# TriacFanout.net
KiCad netlist of a schematic drawn in EAGLE
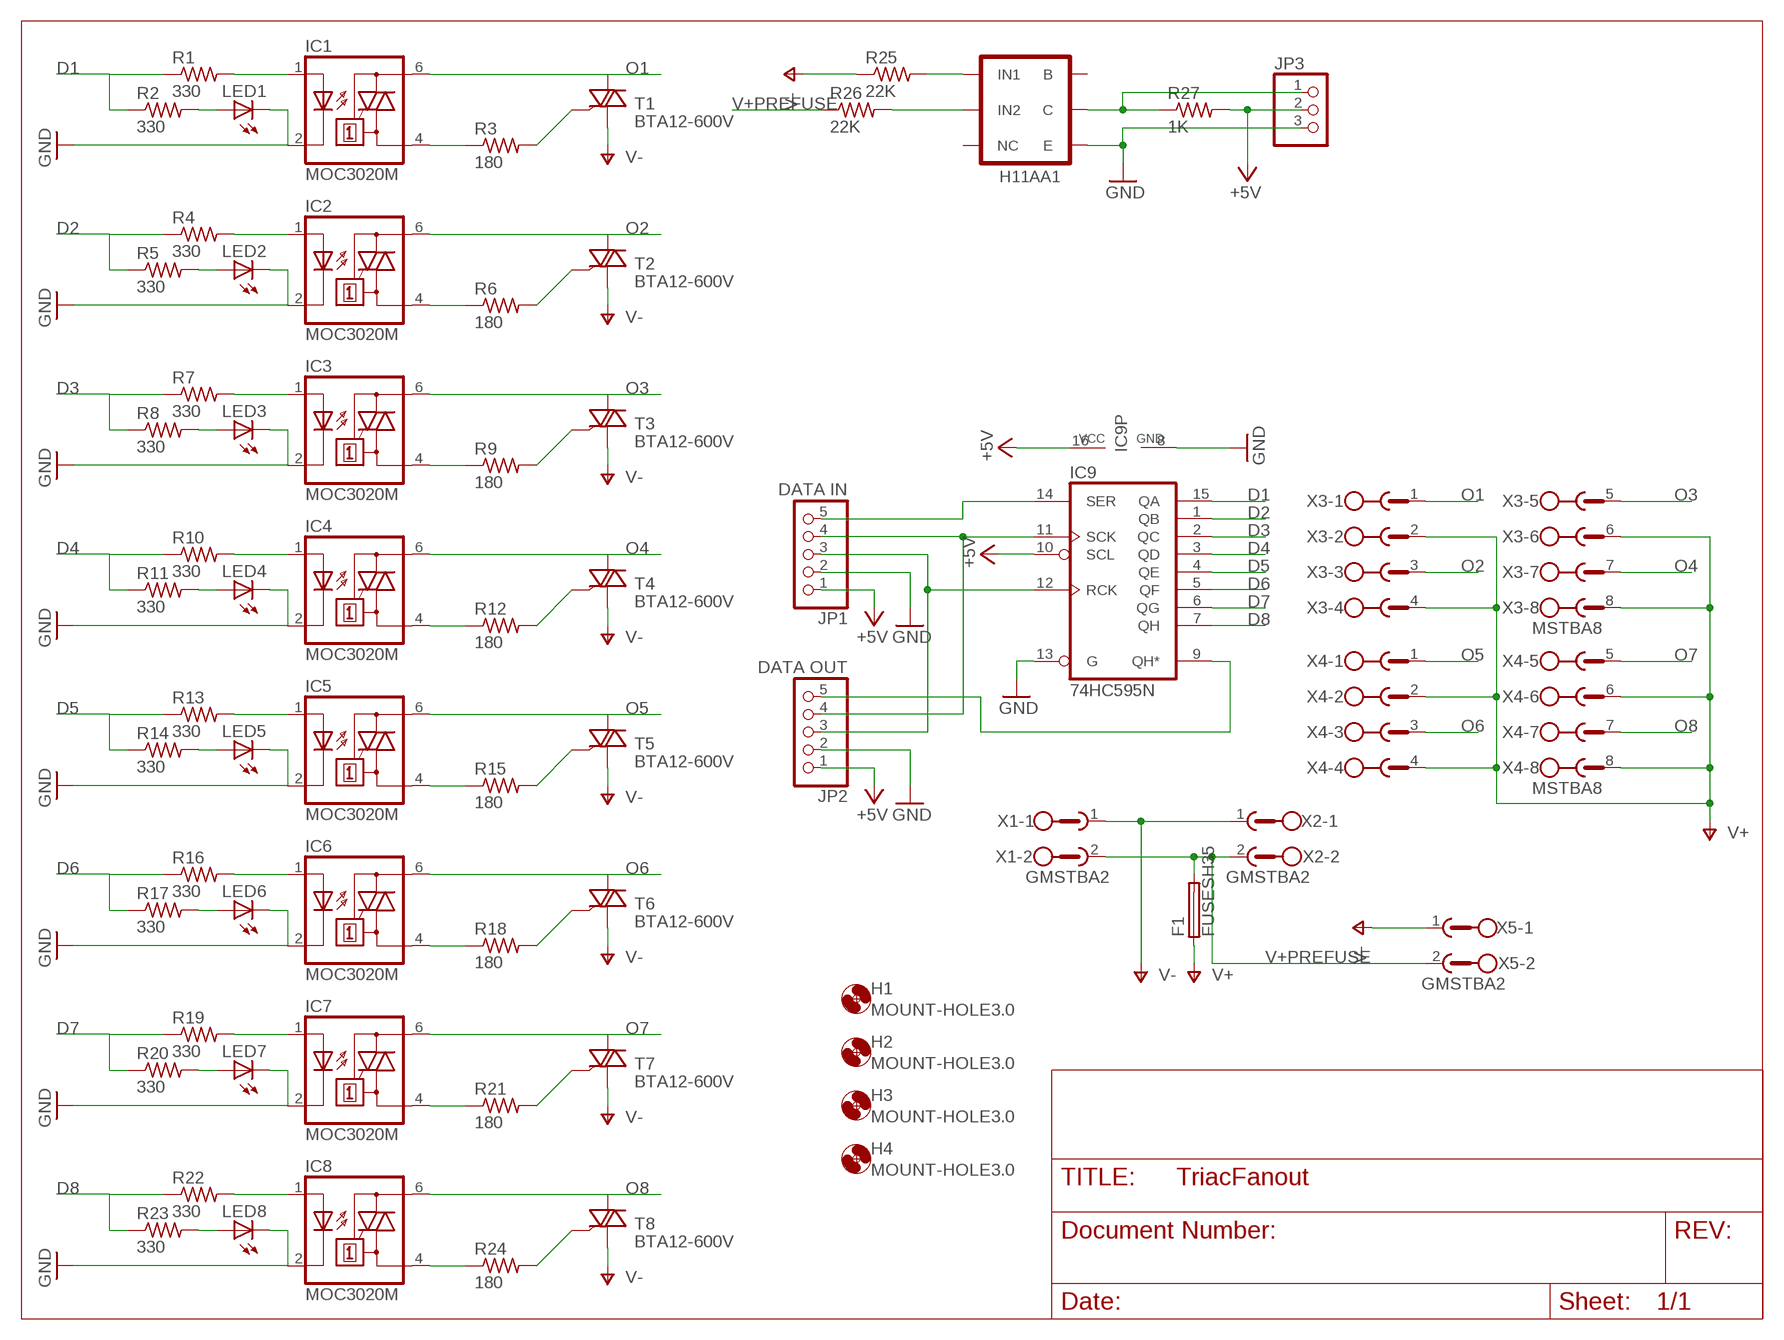
[diagram p0: schematic, sheet 1]

(export (version "E")
  (design (tool "Eeschema 10.0.6"))
  (components
    (comp (ref "F1")
      (value "FUSESH35")
      (footprint "eagle-import:SH25")
      (libsource (lib "eagle-import") (part "FUSESH35"))
    )
    (comp (ref "H1")
      (value "MOUNT-HOLE3.0")
      (footprint "eagle-import:3,0")
      (libsource (lib "eagle-import") (part "MOUNT-HOLE3.0"))
    )
    (comp (ref "H2")
      (value "MOUNT-HOLE3.0")
      (footprint "eagle-import:3,0")
      (libsource (lib "eagle-import") (part "MOUNT-HOLE3.0"))
    )
    (comp (ref "H3")
      (value "MOUNT-HOLE3.0")
      (footprint "eagle-import:3,0")
      (libsource (lib "eagle-import") (part "MOUNT-HOLE3.0"))
    )
    (comp (ref "H4")
      (value "MOUNT-HOLE3.0")
      (footprint "eagle-import:3,0")
      (libsource (lib "eagle-import") (part "MOUNT-HOLE3.0"))
    )
    (comp (ref "IC1")
      (value "MOC3020M")
      (footprint "eagle-import:DIL06")
      (fields (field (name "MF") "FAIRCHILD SEMICONDUCTOR") (field (name "MPN") "MOC3020-M"))
      (libsource (lib "eagle-import") (part "MOC30M20"))
    )
    (comp (ref "IC2")
      (value "MOC3020M")
      (footprint "eagle-import:DIL06")
      (fields (field (name "MF") "FAIRCHILD SEMICONDUCTOR") (field (name "MPN") "MOC3020-M"))
      (libsource (lib "eagle-import") (part "MOC30M20"))
    )
    (comp (ref "IC3")
      (value "MOC3020M")
      (footprint "eagle-import:DIL06")
      (fields (field (name "MF") "FAIRCHILD SEMICONDUCTOR") (field (name "MPN") "MOC3020-M"))
      (libsource (lib "eagle-import") (part "MOC30M20"))
    )
    (comp (ref "IC4")
      (value "MOC3020M")
      (footprint "eagle-import:DIL06")
      (fields (field (name "MF") "FAIRCHILD SEMICONDUCTOR") (field (name "MPN") "MOC3020-M"))
      (libsource (lib "eagle-import") (part "MOC30M20"))
    )
    (comp (ref "IC5")
      (value "MOC3020M")
      (footprint "eagle-import:DIL06")
      (fields (field (name "MF") "FAIRCHILD SEMICONDUCTOR") (field (name "MPN") "MOC3020-M"))
      (libsource (lib "eagle-import") (part "MOC30M20"))
    )
    (comp (ref "IC6")
      (value "MOC3020M")
      (footprint "eagle-import:DIL06")
      (fields (field (name "MF") "FAIRCHILD SEMICONDUCTOR") (field (name "MPN") "MOC3020-M"))
      (libsource (lib "eagle-import") (part "MOC30M20"))
    )
    (comp (ref "IC7")
      (value "MOC3020M")
      (footprint "eagle-import:DIL06")
      (fields (field (name "MF") "FAIRCHILD SEMICONDUCTOR") (field (name "MPN") "MOC3020-M"))
      (libsource (lib "eagle-import") (part "MOC30M20"))
    )
    (comp (ref "IC8")
      (value "MOC3020M")
      (footprint "eagle-import:DIL06")
      (fields (field (name "MF") "FAIRCHILD SEMICONDUCTOR") (field (name "MPN") "MOC3020-M"))
      (libsource (lib "eagle-import") (part "MOC30M20"))
    )
    (comp (ref "IC9")
      (value "74HC595N")
      (footprint "eagle-import:DIL16")
      (libsource (lib "eagle-import") (part "74595NHC"))
    )
    (comp (ref "JP1")
      (value "DATA IN")
      (footprint "eagle-import:1X05")
      (libsource (lib "eagle-import") (part "PINHD-1X5"))
    )
    (comp (ref "JP2")
      (value "DATA OUT")
      (footprint "eagle-import:1X05")
      (libsource (lib "eagle-import") (part "PINHD-1X5"))
    )
    (comp (ref "JP3")
      (value "PINHD-1X3")
      (footprint "eagle-import:1X03")
      (libsource (lib "eagle-import") (part "PINHD-1X3"))
    )
    (comp (ref "LED1")
      (value "LED5MM")
      (footprint "eagle-import:LED5MM")
      (libsource (lib "eagle-import") (part "LED5MM"))
    )
    (comp (ref "LED2")
      (value "LED5MM")
      (footprint "eagle-import:LED5MM")
      (libsource (lib "eagle-import") (part "LED5MM"))
    )
    (comp (ref "LED3")
      (value "LED5MM")
      (footprint "eagle-import:LED5MM")
      (libsource (lib "eagle-import") (part "LED5MM"))
    )
    (comp (ref "LED4")
      (value "LED5MM")
      (footprint "eagle-import:LED5MM")
      (libsource (lib "eagle-import") (part "LED5MM"))
    )
    (comp (ref "LED5")
      (value "LED5MM")
      (footprint "eagle-import:LED5MM")
      (libsource (lib "eagle-import") (part "LED5MM"))
    )
    (comp (ref "LED6")
      (value "LED5MM")
      (footprint "eagle-import:LED5MM")
      (libsource (lib "eagle-import") (part "LED5MM"))
    )
    (comp (ref "LED7")
      (value "LED5MM")
      (footprint "eagle-import:LED5MM")
      (libsource (lib "eagle-import") (part "LED5MM"))
    )
    (comp (ref "LED8")
      (value "LED5MM")
      (footprint "eagle-import:LED5MM")
      (libsource (lib "eagle-import") (part "LED5MM"))
    )
    (comp (ref "R1")
      (value "330")
      (footprint "eagle-import:0207_10")
      (libsource (lib "eagle-import") (part "R-US_0207/10"))
    )
    (comp (ref "R2")
      (value "330")
      (footprint "eagle-import:0207_10")
      (libsource (lib "eagle-import") (part "R-US_0207/10"))
    )
    (comp (ref "R3")
      (value "180")
      (footprint "eagle-import:0207_10")
      (libsource (lib "eagle-import") (part "R-US_0207/10"))
    )
    (comp (ref "R4")
      (value "330")
      (footprint "eagle-import:0207_10")
      (libsource (lib "eagle-import") (part "R-US_0207/10"))
    )
    (comp (ref "R5")
      (value "330")
      (footprint "eagle-import:0207_10")
      (libsource (lib "eagle-import") (part "R-US_0207/10"))
    )
    (comp (ref "R6")
      (value "180")
      (footprint "eagle-import:0207_10")
      (libsource (lib "eagle-import") (part "R-US_0207/10"))
    )
    (comp (ref "R7")
      (value "330")
      (footprint "eagle-import:0207_10")
      (libsource (lib "eagle-import") (part "R-US_0207/10"))
    )
    (comp (ref "R8")
      (value "330")
      (footprint "eagle-import:0207_10")
      (libsource (lib "eagle-import") (part "R-US_0207/10"))
    )
    (comp (ref "R9")
      (value "180")
      (footprint "eagle-import:0207_10")
      (libsource (lib "eagle-import") (part "R-US_0207/10"))
    )
    (comp (ref "R10")
      (value "330")
      (footprint "eagle-import:0207_10")
      (libsource (lib "eagle-import") (part "R-US_0207/10"))
    )
    (comp (ref "R11")
      (value "330")
      (footprint "eagle-import:0207_10")
      (libsource (lib "eagle-import") (part "R-US_0207/10"))
    )
    (comp (ref "R12")
      (value "180")
      (footprint "eagle-import:0207_10")
      (libsource (lib "eagle-import") (part "R-US_0207/10"))
    )
    (comp (ref "R13")
      (value "330")
      (footprint "eagle-import:0207_10")
      (libsource (lib "eagle-import") (part "R-US_0207/10"))
    )
    (comp (ref "R14")
      (value "330")
      (footprint "eagle-import:0207_10")
      (libsource (lib "eagle-import") (part "R-US_0207/10"))
    )
    (comp (ref "R15")
      (value "180")
      (footprint "eagle-import:0207_10")
      (libsource (lib "eagle-import") (part "R-US_0207/10"))
    )
    (comp (ref "R16")
      (value "330")
      (footprint "eagle-import:0207_10")
      (libsource (lib "eagle-import") (part "R-US_0207/10"))
    )
    (comp (ref "R17")
      (value "330")
      (footprint "eagle-import:0207_10")
      (libsource (lib "eagle-import") (part "R-US_0207/10"))
    )
    (comp (ref "R18")
      (value "180")
      (footprint "eagle-import:0207_10")
      (libsource (lib "eagle-import") (part "R-US_0207/10"))
    )
    (comp (ref "R19")
      (value "330")
      (footprint "eagle-import:0207_10")
      (libsource (lib "eagle-import") (part "R-US_0207/10"))
    )
    (comp (ref "R20")
      (value "330")
      (footprint "eagle-import:0207_10")
      (libsource (lib "eagle-import") (part "R-US_0207/10"))
    )
    (comp (ref "R21")
      (value "180")
      (footprint "eagle-import:0207_10")
      (libsource (lib "eagle-import") (part "R-US_0207/10"))
    )
    (comp (ref "R22")
      (value "330")
      (footprint "eagle-import:0207_10")
      (libsource (lib "eagle-import") (part "R-US_0207/10"))
    )
    (comp (ref "R23")
      (value "330")
      (footprint "eagle-import:0207_10")
      (libsource (lib "eagle-import") (part "R-US_0207/10"))
    )
    (comp (ref "R24")
      (value "180")
      (footprint "eagle-import:0207_10")
      (libsource (lib "eagle-import") (part "R-US_0207/10"))
    )
    (comp (ref "R25")
      (value "22K")
      (footprint "eagle-import:0411_12")
      (libsource (lib "eagle-import") (part "R-US_0411/12"))
    )
    (comp (ref "R26")
      (value "22K")
      (footprint "eagle-import:0411_12")
      (libsource (lib "eagle-import") (part "R-US_0411/12"))
    )
    (comp (ref "R27")
      (value "1K")
      (footprint "eagle-import:0207_10")
      (libsource (lib "eagle-import") (part "R-US_0207/10"))
    )
    (comp (ref "T1")
      (value "BTA12-600V")
      (footprint "eagle-import:TO220V")
      (libsource (lib "eagle-import") (part "BTA12-600V"))
    )
    (comp (ref "T2")
      (value "BTA12-600V")
      (footprint "eagle-import:TO220V")
      (libsource (lib "eagle-import") (part "BTA12-600V"))
    )
    (comp (ref "T3")
      (value "BTA12-600V")
      (footprint "eagle-import:TO220V")
      (libsource (lib "eagle-import") (part "BTA12-600V"))
    )
    (comp (ref "T4")
      (value "BTA12-600V")
      (footprint "eagle-import:TO220V")
      (libsource (lib "eagle-import") (part "BTA12-600V"))
    )
    (comp (ref "T5")
      (value "BTA12-600V")
      (footprint "eagle-import:TO220V")
      (libsource (lib "eagle-import") (part "BTA12-600V"))
    )
    (comp (ref "T6")
      (value "BTA12-600V")
      (footprint "eagle-import:TO220V")
      (libsource (lib "eagle-import") (part "BTA12-600V"))
    )
    (comp (ref "T7")
      (value "BTA12-600V")
      (footprint "eagle-import:TO220V")
      (libsource (lib "eagle-import") (part "BTA12-600V"))
    )
    (comp (ref "T8")
      (value "BTA12-600V")
      (footprint "eagle-import:TO220V")
      (libsource (lib "eagle-import") (part "BTA12-600V"))
    )
    (comp (ref "U$1")
      (value "H11AA1")
      (footprint "eagle-import:DIL06")
      (libsource (lib "eagle-import") (part "H11AA1"))
    )
    (comp (ref "X1")
      (value "GMSTBA2")
      (footprint "eagle-import:GMSTBA2")
      (fields (field (name "MF") "FARNELL") (field (name "MPN") "1757242"))
      (libsource (lib "eagle-import") (part "GMSTBA2"))
    )
    (comp (ref "X2")
      (value "GMSTBA2")
      (footprint "eagle-import:GMSTBA2")
      (fields (field (name "MF") "FARNELL") (field (name "MPN") "1757242"))
      (libsource (lib "eagle-import") (part "GMSTBA2"))
    )
    (comp (ref "X3")
      (value "MSTBA8")
      (footprint "eagle-import:MSTBA8")
      (fields (field (name "MF") "FARNELL") (field (name "MPN") "1757307"))
      (libsource (lib "eagle-import") (part "MSTBA8"))
    )
    (comp (ref "X4")
      (value "MSTBA8")
      (footprint "eagle-import:MSTBA8")
      (fields (field (name "MF") "FARNELL") (field (name "MPN") "1757307"))
      (libsource (lib "eagle-import") (part "MSTBA8"))
    )
    (comp (ref "X5")
      (value "GMSTBA2")
      (footprint "eagle-import:GMSTBA2")
      (fields (field (name "MF") "FARNELL") (field (name "MPN") "1757242"))
      (libsource (lib "eagle-import") (part "GMSTBA2"))
    )
  )
  (nets
    (net (code "1") (name "+5V") (class "Default")
      (node (ref "IC9") (pin "10") (pinfunction "SCL_10") (pintype "input"))
      (node (ref "IC9") (pin "16") (pinfunction "VCC_16") (pintype "power_in"))
      (node (ref "JP1") (pin "1") (pinfunction "1_1") (pintype "passive"))
      (node (ref "JP2") (pin "1") (pinfunction "1_1") (pintype "passive"))
      (node (ref "JP3") (pin "2") (pinfunction "2_2") (pintype "passive"))
      (node (ref "R27") (pin "2") (pinfunction "2_2") (pintype "passive"))
    )
    (net (code "2") (name "/D1") (class "Default")
      (node (ref "IC9") (pin "15") (pinfunction "QA_15") (pintype "tri_state"))
      (node (ref "R1") (pin "1") (pinfunction "1_1") (pintype "passive"))
      (node (ref "R2") (pin "1") (pinfunction "1_1") (pintype "passive"))
    )
    (net (code "3") (name "/D2") (class "Default")
      (node (ref "IC9") (pin "1") (pinfunction "QB_1") (pintype "tri_state"))
      (node (ref "R4") (pin "1") (pinfunction "1_1") (pintype "passive"))
      (node (ref "R5") (pin "1") (pinfunction "1_1") (pintype "passive"))
    )
    (net (code "4") (name "/D3") (class "Default")
      (node (ref "IC9") (pin "2") (pinfunction "QC_2") (pintype "tri_state"))
      (node (ref "R7") (pin "1") (pinfunction "1_1") (pintype "passive"))
      (node (ref "R8") (pin "1") (pinfunction "1_1") (pintype "passive"))
    )
    (net (code "5") (name "/D4") (class "Default")
      (node (ref "IC9") (pin "3") (pinfunction "QD_3") (pintype "tri_state"))
      (node (ref "R10") (pin "1") (pinfunction "1_1") (pintype "passive"))
      (node (ref "R11") (pin "1") (pinfunction "1_1") (pintype "passive"))
    )
    (net (code "6") (name "/D5") (class "Default")
      (node (ref "IC9") (pin "4") (pinfunction "QE_4") (pintype "tri_state"))
      (node (ref "R13") (pin "1") (pinfunction "1_1") (pintype "passive"))
      (node (ref "R14") (pin "1") (pinfunction "1_1") (pintype "passive"))
    )
    (net (code "7") (name "/D6") (class "Default")
      (node (ref "IC9") (pin "5") (pinfunction "QF_5") (pintype "tri_state"))
      (node (ref "R16") (pin "1") (pinfunction "1_1") (pintype "passive"))
      (node (ref "R17") (pin "1") (pinfunction "1_1") (pintype "passive"))
    )
    (net (code "8") (name "/D7") (class "Default")
      (node (ref "IC9") (pin "6") (pinfunction "QG_6") (pintype "tri_state"))
      (node (ref "R19") (pin "1") (pinfunction "1_1") (pintype "passive"))
      (node (ref "R20") (pin "1") (pinfunction "1_1") (pintype "passive"))
    )
    (net (code "9") (name "/D8") (class "Default")
      (node (ref "IC9") (pin "7") (pinfunction "QH_7") (pintype "tri_state"))
      (node (ref "R22") (pin "1") (pinfunction "1_1") (pintype "passive"))
      (node (ref "R23") (pin "1") (pinfunction "1_1") (pintype "passive"))
    )
    (net (code "10") (name "/O1") (class "Default")
      (node (ref "IC1") (pin "6") (pinfunction "A2_6") (pintype "passive"))
      (node (ref "T1") (pin "2") (pinfunction "A2_2") (pintype "passive"))
      (node (ref "X3") (pin "1") (pinfunction "1_1") (pintype "passive"))
    )
    (net (code "11") (name "/O2") (class "Default")
      (node (ref "IC2") (pin "6") (pinfunction "A2_6") (pintype "passive"))
      (node (ref "T2") (pin "2") (pinfunction "A2_2") (pintype "passive"))
      (node (ref "X3") (pin "3") (pinfunction "1_3") (pintype "passive"))
    )
    (net (code "12") (name "/O3") (class "Default")
      (node (ref "IC3") (pin "6") (pinfunction "A2_6") (pintype "passive"))
      (node (ref "T3") (pin "2") (pinfunction "A2_2") (pintype "passive"))
      (node (ref "X3") (pin "5") (pinfunction "1_5") (pintype "passive"))
    )
    (net (code "13") (name "/O4") (class "Default")
      (node (ref "IC4") (pin "6") (pinfunction "A2_6") (pintype "passive"))
      (node (ref "T4") (pin "2") (pinfunction "A2_2") (pintype "passive"))
      (node (ref "X3") (pin "7") (pinfunction "1_7") (pintype "passive"))
    )
    (net (code "14") (name "/O5") (class "Default")
      (node (ref "IC5") (pin "6") (pinfunction "A2_6") (pintype "passive"))
      (node (ref "T5") (pin "2") (pinfunction "A2_2") (pintype "passive"))
      (node (ref "X4") (pin "1") (pinfunction "1_1") (pintype "passive"))
    )
    (net (code "15") (name "/O6") (class "Default")
      (node (ref "IC6") (pin "6") (pinfunction "A2_6") (pintype "passive"))
      (node (ref "T6") (pin "2") (pinfunction "A2_2") (pintype "passive"))
      (node (ref "X4") (pin "3") (pinfunction "1_3") (pintype "passive"))
    )
    (net (code "16") (name "/O7") (class "Default")
      (node (ref "IC7") (pin "6") (pinfunction "A2_6") (pintype "passive"))
      (node (ref "T7") (pin "2") (pinfunction "A2_2") (pintype "passive"))
      (node (ref "X4") (pin "5") (pinfunction "1_5") (pintype "passive"))
    )
    (net (code "17") (name "/O8") (class "Default")
      (node (ref "IC8") (pin "6") (pinfunction "A2_6") (pintype "passive"))
      (node (ref "T8") (pin "2") (pinfunction "A2_2") (pintype "passive"))
      (node (ref "X4") (pin "7") (pinfunction "1_7") (pintype "passive"))
    )
    (net (code "18") (name "/V+PREFUSE") (class "Default")
      (node (ref "F1") (pin "2") (pinfunction "2_2") (pintype "passive"))
      (node (ref "R26") (pin "1") (pinfunction "1_1") (pintype "passive"))
      (node (ref "X1") (pin "2") (pinfunction "1_2") (pintype "passive"))
      (node (ref "X2") (pin "2") (pinfunction "1_2") (pintype "passive"))
      (node (ref "X5") (pin "2") (pinfunction "1_2") (pintype "passive"))
    )
    (net (code "19") (name "GND") (class "Default")
      (node (ref "IC1") (pin "2") (pinfunction "C_2") (pintype "passive"))
      (node (ref "IC2") (pin "2") (pinfunction "C_2") (pintype "passive"))
      (node (ref "IC3") (pin "2") (pinfunction "C_2") (pintype "passive"))
      (node (ref "IC4") (pin "2") (pinfunction "C_2") (pintype "passive"))
      (node (ref "IC5") (pin "2") (pinfunction "C_2") (pintype "passive"))
      (node (ref "IC6") (pin "2") (pinfunction "C_2") (pintype "passive"))
      (node (ref "IC7") (pin "2") (pinfunction "C_2") (pintype "passive"))
      (node (ref "IC8") (pin "2") (pinfunction "C_2") (pintype "passive"))
      (node (ref "IC9") (pin "13") (pinfunction "G_13") (pintype "input"))
      (node (ref "IC9") (pin "8") (pinfunction "GND_8") (pintype "power_in"))
      (node (ref "JP1") (pin "2") (pinfunction "2_2") (pintype "passive"))
      (node (ref "JP2") (pin "2") (pinfunction "2_2") (pintype "passive"))
      (node (ref "JP3") (pin "3") (pinfunction "3_3") (pintype "passive"))
      (node (ref "LED1") (pin "K") (pinfunction "C_K") (pintype "passive"))
      (node (ref "LED2") (pin "K") (pinfunction "C_K") (pintype "passive"))
      (node (ref "LED3") (pin "K") (pinfunction "C_K") (pintype "passive"))
      (node (ref "LED4") (pin "K") (pinfunction "C_K") (pintype "passive"))
      (node (ref "LED5") (pin "K") (pinfunction "C_K") (pintype "passive"))
      (node (ref "LED6") (pin "K") (pinfunction "C_K") (pintype "passive"))
      (node (ref "LED7") (pin "K") (pinfunction "C_K") (pintype "passive"))
      (node (ref "LED8") (pin "K") (pinfunction "C_K") (pintype "passive"))
      (node (ref "U$1") (pin "4") (pinfunction "E_4") (pintype "bidirectional"))
    )
    (net (code "20") (name "Net-(IC1-A)") (class "Default")
      (node (ref "IC1") (pin "1") (pinfunction "A_1") (pintype "passive"))
      (node (ref "R1") (pin "2") (pinfunction "2_2") (pintype "passive"))
    )
    (net (code "21") (name "Net-(IC1-A1)") (class "Default")
      (node (ref "IC1") (pin "4") (pinfunction "A1_4") (pintype "passive"))
      (node (ref "R3") (pin "1") (pinfunction "1_1") (pintype "passive"))
    )
    (net (code "22") (name "Net-(IC2-A)") (class "Default")
      (node (ref "IC2") (pin "1") (pinfunction "A_1") (pintype "passive"))
      (node (ref "R4") (pin "2") (pinfunction "2_2") (pintype "passive"))
    )
    (net (code "23") (name "Net-(IC2-A1)") (class "Default")
      (node (ref "IC2") (pin "4") (pinfunction "A1_4") (pintype "passive"))
      (node (ref "R6") (pin "1") (pinfunction "1_1") (pintype "passive"))
    )
    (net (code "24") (name "Net-(IC3-A)") (class "Default")
      (node (ref "IC3") (pin "1") (pinfunction "A_1") (pintype "passive"))
      (node (ref "R7") (pin "2") (pinfunction "2_2") (pintype "passive"))
    )
    (net (code "25") (name "Net-(IC3-A1)") (class "Default")
      (node (ref "IC3") (pin "4") (pinfunction "A1_4") (pintype "passive"))
      (node (ref "R9") (pin "1") (pinfunction "1_1") (pintype "passive"))
    )
    (net (code "26") (name "Net-(IC4-A)") (class "Default")
      (node (ref "IC4") (pin "1") (pinfunction "A_1") (pintype "passive"))
      (node (ref "R10") (pin "2") (pinfunction "2_2") (pintype "passive"))
    )
    (net (code "27") (name "Net-(IC4-A1)") (class "Default")
      (node (ref "IC4") (pin "4") (pinfunction "A1_4") (pintype "passive"))
      (node (ref "R12") (pin "1") (pinfunction "1_1") (pintype "passive"))
    )
    (net (code "28") (name "Net-(IC5-A)") (class "Default")
      (node (ref "IC5") (pin "1") (pinfunction "A_1") (pintype "passive"))
      (node (ref "R13") (pin "2") (pinfunction "2_2") (pintype "passive"))
    )
    (net (code "29") (name "Net-(IC5-A1)") (class "Default")
      (node (ref "IC5") (pin "4") (pinfunction "A1_4") (pintype "passive"))
      (node (ref "R15") (pin "1") (pinfunction "1_1") (pintype "passive"))
    )
    (net (code "30") (name "Net-(IC6-A)") (class "Default")
      (node (ref "IC6") (pin "1") (pinfunction "A_1") (pintype "passive"))
      (node (ref "R16") (pin "2") (pinfunction "2_2") (pintype "passive"))
    )
    (net (code "31") (name "Net-(IC6-A1)") (class "Default")
      (node (ref "IC6") (pin "4") (pinfunction "A1_4") (pintype "passive"))
      (node (ref "R18") (pin "1") (pinfunction "1_1") (pintype "passive"))
    )
    (net (code "32") (name "Net-(IC7-A)") (class "Default")
      (node (ref "IC7") (pin "1") (pinfunction "A_1") (pintype "passive"))
      (node (ref "R19") (pin "2") (pinfunction "2_2") (pintype "passive"))
    )
    (net (code "33") (name "Net-(IC7-A1)") (class "Default")
      (node (ref "IC7") (pin "4") (pinfunction "A1_4") (pintype "passive"))
      (node (ref "R21") (pin "1") (pinfunction "1_1") (pintype "passive"))
    )
    (net (code "34") (name "Net-(IC8-A)") (class "Default")
      (node (ref "IC8") (pin "1") (pinfunction "A_1") (pintype "passive"))
      (node (ref "R22") (pin "2") (pinfunction "2_2") (pintype "passive"))
    )
    (net (code "35") (name "Net-(IC8-A1)") (class "Default")
      (node (ref "IC8") (pin "4") (pinfunction "A1_4") (pintype "passive"))
      (node (ref "R24") (pin "1") (pinfunction "1_1") (pintype "passive"))
    )
    (net (code "36") (name "Net-(IC9A-QH*)") (class "Default")
      (node (ref "IC9") (pin "9") (pinfunction "QH*_9") (pintype "tri_state"))
      (node (ref "JP2") (pin "5") (pinfunction "5_5") (pintype "passive"))
    )
    (net (code "37") (name "Net-(IC9A-RCK)") (class "Default")
      (node (ref "IC9") (pin "12") (pinfunction "RCK_12") (pintype "input"))
      (node (ref "JP1") (pin "3") (pinfunction "3_3") (pintype "passive"))
      (node (ref "JP2") (pin "3") (pinfunction "3_3") (pintype "passive"))
    )
    (net (code "38") (name "Net-(IC9A-SCK)") (class "Default")
      (node (ref "IC9") (pin "11") (pinfunction "SCK_11") (pintype "input"))
      (node (ref "JP1") (pin "4") (pinfunction "4_4") (pintype "passive"))
      (node (ref "JP2") (pin "4") (pinfunction "4_4") (pintype "passive"))
    )
    (net (code "39") (name "Net-(IC9A-SER)") (class "Default")
      (node (ref "IC9") (pin "14") (pinfunction "SER_14") (pintype "input"))
      (node (ref "JP1") (pin "5") (pinfunction "5_5") (pintype "passive"))
    )
    (net (code "40") (name "Net-(LED1-PadA)") (class "Default")
      (node (ref "LED1") (pin "A") (pinfunction "A_A") (pintype "passive"))
      (node (ref "R2") (pin "2") (pinfunction "2_2") (pintype "passive"))
    )
    (net (code "41") (name "Net-(LED2-PadA)") (class "Default")
      (node (ref "LED2") (pin "A") (pinfunction "A_A") (pintype "passive"))
      (node (ref "R5") (pin "2") (pinfunction "2_2") (pintype "passive"))
    )
    (net (code "42") (name "Net-(LED3-PadA)") (class "Default")
      (node (ref "LED3") (pin "A") (pinfunction "A_A") (pintype "passive"))
      (node (ref "R8") (pin "2") (pinfunction "2_2") (pintype "passive"))
    )
    (net (code "43") (name "Net-(LED4-PadA)") (class "Default")
      (node (ref "LED4") (pin "A") (pinfunction "A_A") (pintype "passive"))
      (node (ref "R11") (pin "2") (pinfunction "2_2") (pintype "passive"))
    )
    (net (code "44") (name "Net-(LED5-PadA)") (class "Default")
      (node (ref "LED5") (pin "A") (pinfunction "A_A") (pintype "passive"))
      (node (ref "R14") (pin "2") (pinfunction "2_2") (pintype "passive"))
    )
    (net (code "45") (name "Net-(LED6-PadA)") (class "Default")
      (node (ref "LED6") (pin "A") (pinfunction "A_A") (pintype "passive"))
      (node (ref "R17") (pin "2") (pinfunction "2_2") (pintype "passive"))
    )
    (net (code "46") (name "Net-(LED7-PadA)") (class "Default")
      (node (ref "LED7") (pin "A") (pinfunction "A_A") (pintype "passive"))
      (node (ref "R20") (pin "2") (pinfunction "2_2") (pintype "passive"))
    )
    (net (code "47") (name "Net-(LED8-PadA)") (class "Default")
      (node (ref "LED8") (pin "A") (pinfunction "A_A") (pintype "passive"))
      (node (ref "R23") (pin "2") (pinfunction "2_2") (pintype "passive"))
    )
    (net (code "48") (name "Net-(T1-G)") (class "Default")
      (node (ref "R3") (pin "2") (pinfunction "2_2") (pintype "passive"))
      (node (ref "T1") (pin "3") (pinfunction "G_3") (pintype "passive"))
    )
    (net (code "49") (name "Net-(T2-G)") (class "Default")
      (node (ref "R6") (pin "2") (pinfunction "2_2") (pintype "passive"))
      (node (ref "T2") (pin "3") (pinfunction "G_3") (pintype "passive"))
    )
    (net (code "50") (name "Net-(T3-G)") (class "Default")
      (node (ref "R9") (pin "2") (pinfunction "2_2") (pintype "passive"))
      (node (ref "T3") (pin "3") (pinfunction "G_3") (pintype "passive"))
    )
    (net (code "51") (name "Net-(T4-G)") (class "Default")
      (node (ref "R12") (pin "2") (pinfunction "2_2") (pintype "passive"))
      (node (ref "T4") (pin "3") (pinfunction "G_3") (pintype "passive"))
    )
    (net (code "52") (name "Net-(T5-G)") (class "Default")
      (node (ref "R15") (pin "2") (pinfunction "2_2") (pintype "passive"))
      (node (ref "T5") (pin "3") (pinfunction "G_3") (pintype "passive"))
    )
    (net (code "53") (name "Net-(T6-G)") (class "Default")
      (node (ref "R18") (pin "2") (pinfunction "2_2") (pintype "passive"))
      (node (ref "T6") (pin "3") (pinfunction "G_3") (pintype "passive"))
    )
    (net (code "54") (name "Net-(T7-G)") (class "Default")
      (node (ref "R21") (pin "2") (pinfunction "2_2") (pintype "passive"))
      (node (ref "T7") (pin "3") (pinfunction "G_3") (pintype "passive"))
    )
    (net (code "55") (name "Net-(T8-G)") (class "Default")
      (node (ref "R24") (pin "2") (pinfunction "2_2") (pintype "passive"))
      (node (ref "T8") (pin "3") (pinfunction "G_3") (pintype "passive"))
    )
    (net (code "56") (name "Net-(U$1-C)") (class "Default")
      (node (ref "JP3") (pin "1") (pinfunction "1_1") (pintype "passive"))
      (node (ref "R27") (pin "1") (pinfunction "1_1") (pintype "passive"))
      (node (ref "U$1") (pin "5") (pinfunction "C_5") (pintype "bidirectional"))
    )
    (net (code "57") (name "Net-(U$1-IN1)") (class "Default")
      (node (ref "R25") (pin "2") (pinfunction "2_2") (pintype "passive"))
      (node (ref "U$1") (pin "1") (pinfunction "IN1_1") (pintype "bidirectional"))
    )
    (net (code "58") (name "Net-(U$1-IN2)") (class "Default")
      (node (ref "R26") (pin "2") (pinfunction "2_2") (pintype "passive"))
      (node (ref "U$1") (pin "2") (pinfunction "IN2_2") (pintype "bidirectional"))
    )
    (net (code "59") (name "V+") (class "Default")
      (node (ref "F1") (pin "1") (pinfunction "1_1") (pintype "passive"))
      (node (ref "X3") (pin "2") (pinfunction "1_2") (pintype "passive"))
      (node (ref "X3") (pin "4") (pinfunction "1_4") (pintype "passive"))
      (node (ref "X3") (pin "6") (pinfunction "1_6") (pintype "passive"))
      (node (ref "X3") (pin "8") (pinfunction "1_8") (pintype "passive"))
      (node (ref "X4") (pin "2") (pinfunction "1_2") (pintype "passive"))
      (node (ref "X4") (pin "4") (pinfunction "1_4") (pintype "passive"))
      (node (ref "X4") (pin "6") (pinfunction "1_6") (pintype "passive"))
      (node (ref "X4") (pin "8") (pinfunction "1_8") (pintype "passive"))
    )
    (net (code "60") (name "V-") (class "Default")
      (node (ref "R25") (pin "1") (pinfunction "1_1") (pintype "passive"))
      (node (ref "T1") (pin "1") (pinfunction "A1_1") (pintype "passive"))
      (node (ref "T2") (pin "1") (pinfunction "A1_1") (pintype "passive"))
      (node (ref "T3") (pin "1") (pinfunction "A1_1") (pintype "passive"))
      (node (ref "T4") (pin "1") (pinfunction "A1_1") (pintype "passive"))
      (node (ref "T5") (pin "1") (pinfunction "A1_1") (pintype "passive"))
      (node (ref "T6") (pin "1") (pinfunction "A1_1") (pintype "passive"))
      (node (ref "T7") (pin "1") (pinfunction "A1_1") (pintype "passive"))
      (node (ref "T8") (pin "1") (pinfunction "A1_1") (pintype "passive"))
      (node (ref "X1") (pin "1") (pinfunction "1_1") (pintype "passive"))
      (node (ref "X2") (pin "1") (pinfunction "1_1") (pintype "passive"))
      (node (ref "X5") (pin "1") (pinfunction "1_1") (pintype "passive"))
    )
    (net (code "61") (name "unconnected-(U$1-B-Pad6)") (class "Default")
      (node (ref "U$1") (pin "6") (pinfunction "B_6") (pintype "bidirectional"))
    )
    (net (code "62") (name "unconnected-(U$1-NC-Pad3)") (class "Default")
      (node (ref "U$1") (pin "3") (pinfunction "NC_3") (pintype "no_connect"))
    )
  )
)
